# FOTA_MicroController.net
KiCad netlist of a schematic drawn in Altium Designer
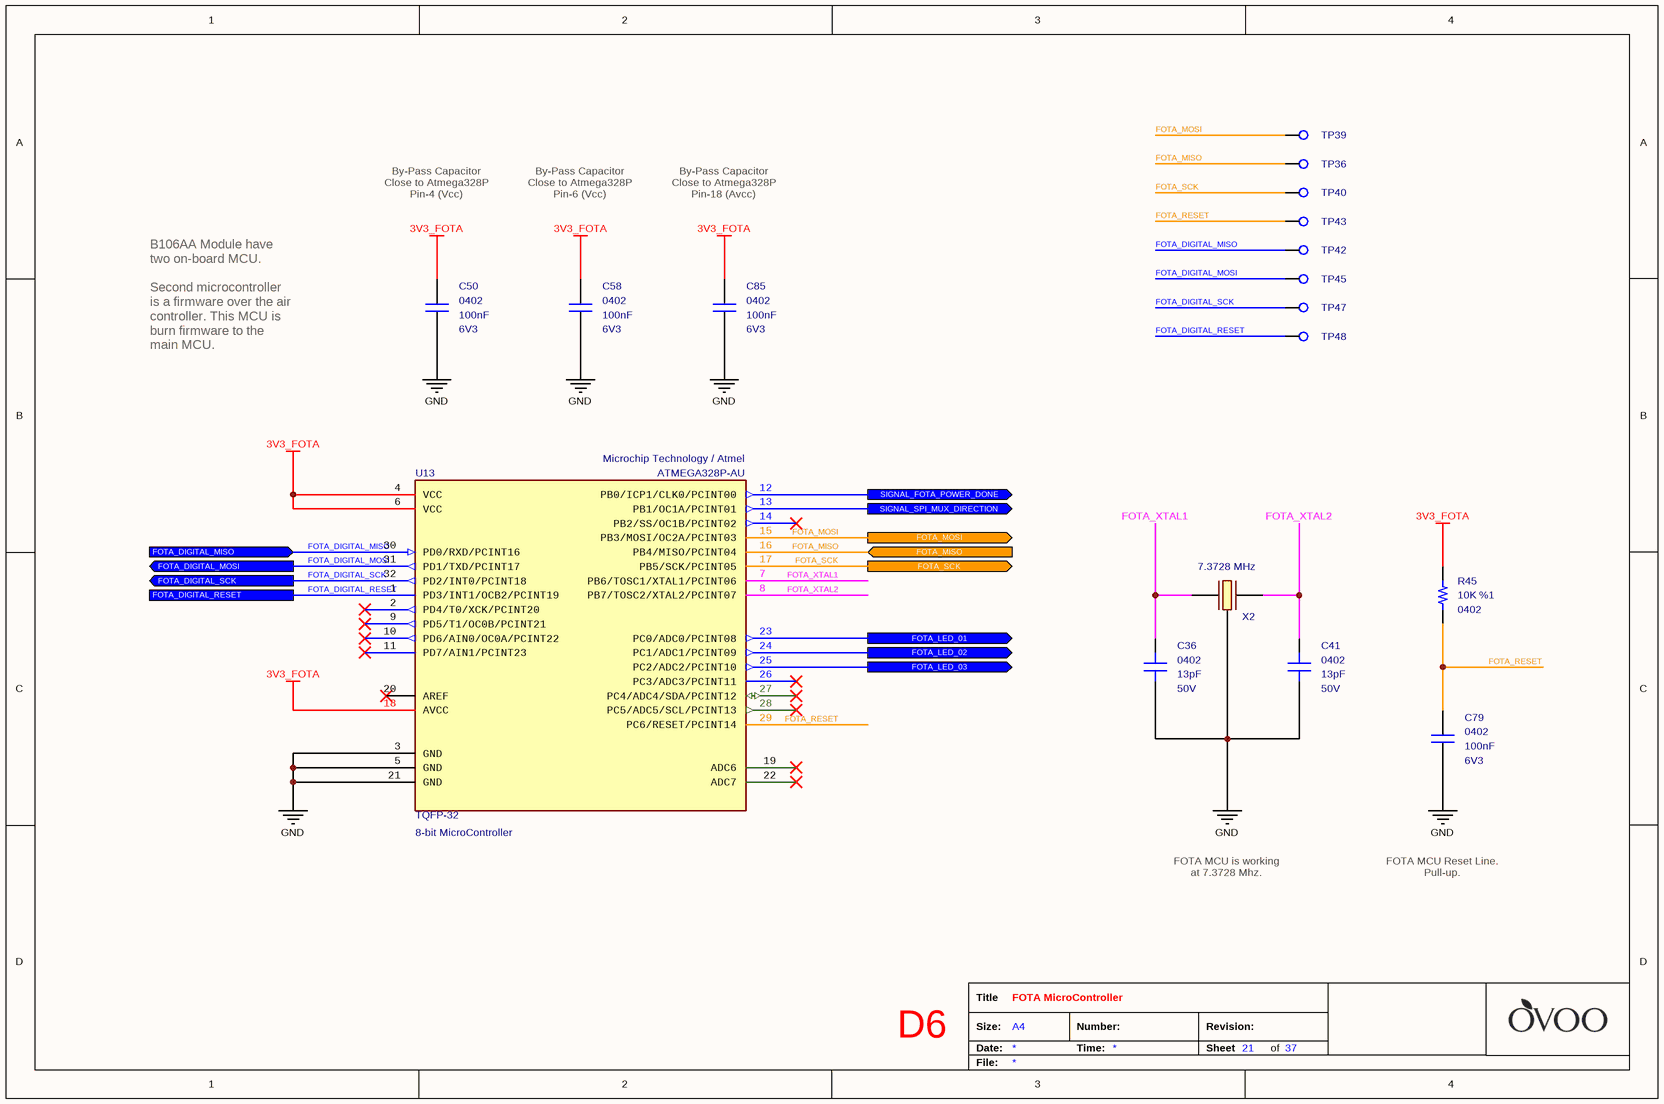
[diagram p0: FOTA MicroController.SchDoc]

(export (version "E")
  (design (tool "Eeschema 10.0.6"))
  (components
    (comp (ref "C36")
      (value "13pF")
      (footprint "CAPACITOR_0402")
      (description "Capacitor - 13pF [0402] (Ceramic)")
      (fields
        (field (name "MANUFACTURER_PART_NUMBER") "CBR04C130F5GAC")
        (field (name "MOUSER_PART_NUMBER") "80-CBR04C130F5GAC")
        (field (name "VOLTAGE") "50V")
        (field (name "CASE") "0402")
      )
      (libsource (lib "Ovoo_Schematic") (part "Capacitor - 13pF [0402-50V)"))
    )
    (comp (ref "C41")
      (value "13pF")
      (footprint "CAPACITOR_0402")
      (description "Capacitor - 13pF [0402] (Ceramic)")
      (fields
        (field (name "MANUFACTURER_PART_NUMBER") "CBR04C130F5GAC")
        (field (name "MOUSER_PART_NUMBER") "80-CBR04C130F5GAC")
        (field (name "VOLTAGE") "50V")
        (field (name "CASE") "0402")
      )
      (libsource (lib "Ovoo_Schematic") (part "Capacitor - 13pF [0402-50V)"))
    )
    (comp (ref "C50")
      (value "100nF")
      (footprint "CAPACITOR_0402")
      (description "Capacitor - 100nF [0402-6V3] (Ceramic)")
      (fields
        (field (name "MANUFACTURER_PART_NUMBER") "04026D104KAT4A")
        (field (name "MOUSER_PART_NUMBER") "581-04026D104KAT4A")
        (field (name "CASE") "0402")
        (field (name "VOLTAGE") "6V3")
      )
      (libsource (lib "Ovoo_Schematic") (part "Capacitor - 100nF [0402-6V3]"))
    )
    (comp (ref "C58")
      (value "100nF")
      (footprint "CAPACITOR_0402")
      (description "Capacitor - 100nF [0402-6V3] (Ceramic)")
      (fields
        (field (name "MANUFACTURER_PART_NUMBER") "04026D104KAT4A")
        (field (name "MOUSER_PART_NUMBER") "581-04026D104KAT4A")
        (field (name "CASE") "0402")
        (field (name "VOLTAGE") "6V3")
      )
      (libsource (lib "Ovoo_Schematic") (part "Capacitor - 100nF [0402-6V3]"))
    )
    (comp (ref "C79")
      (value "100nF")
      (footprint "CAPACITOR_0402")
      (description "Capacitor - 100nF [0402-6V3] (Ceramic)")
      (fields
        (field (name "MANUFACTURER_PART_NUMBER") "04026D104KAT4A")
        (field (name "MOUSER_PART_NUMBER") "581-04026D104KAT4A")
        (field (name "CASE") "0402")
        (field (name "VOLTAGE") "6V3")
      )
      (libsource (lib "Ovoo_Schematic") (part "Capacitor - 100nF [0402-6V3]"))
    )
    (comp (ref "C85")
      (value "100nF")
      (footprint "CAPACITOR_0402")
      (description "Capacitor - 100nF [0402-6V3] (Ceramic)")
      (fields
        (field (name "MANUFACTURER_PART_NUMBER") "04026D104KAT4A")
        (field (name "MOUSER_PART_NUMBER") "581-04026D104KAT4A")
        (field (name "CASE") "0402")
        (field (name "VOLTAGE") "6V3")
      )
      (libsource (lib "Ovoo_Schematic") (part "Capacitor - 100nF [0402-6V3]"))
    )
    (comp (ref "R45")
      (value "10K")
      (footprint "RESISTOR_0402")
      (description "Thick Film Resistors - SMD 1/16 W 10 Kohms 1%")
      (fields
        (field (name "MANUFACTURER_PART_NUMBER") "CRCW040210K0FKED")
        (field (name "MOUSER_PART_NUMBER") "71-CRCW0402-10K-E3")
        (field (name "TOLERANCE") "%1")
        (field (name "CASE") "0402")
      )
      (libsource (lib "Ovoo_Schematic") (part "Resistor - 10K"))
    )
    (comp (ref "TP36")
      (value "PCB - Test Point")
      (footprint "Test_Pad - Hole")
      (description "Test Point")
      (libsource (lib "Ovoo_Schematic") (part "PCB - Test Point"))
    )
    (comp (ref "TP39")
      (value "PCB - Test Point")
      (footprint "Test_Pad - Hole")
      (description "Test Point")
      (libsource (lib "Ovoo_Schematic") (part "PCB - Test Point"))
    )
    (comp (ref "TP40")
      (value "PCB - Test Point")
      (footprint "Test_Pad - Hole")
      (description "Test Point")
      (libsource (lib "Ovoo_Schematic") (part "PCB - Test Point"))
    )
    (comp (ref "TP42")
      (value "PCB - Test Point")
      (footprint "Test_Pad - Hole")
      (description "Test Point")
      (libsource (lib "Ovoo_Schematic") (part "PCB - Test Point"))
    )
    (comp (ref "TP43")
      (value "PCB - Test Point")
      (footprint "Test_Pad - Hole")
      (description "Test Point")
      (libsource (lib "Ovoo_Schematic") (part "PCB - Test Point"))
    )
    (comp (ref "TP45")
      (value "PCB - Test Point")
      (footprint "Test_Pad - Hole")
      (description "Test Point")
      (libsource (lib "Ovoo_Schematic") (part "PCB - Test Point"))
    )
    (comp (ref "TP47")
      (value "PCB - Test Point")
      (footprint "Test_Pad - Hole")
      (description "Test Point")
      (libsource (lib "Ovoo_Schematic") (part "PCB - Test Point"))
    )
    (comp (ref "TP48")
      (value "PCB - Test Point")
      (footprint "Test_Pad - Hole")
      (description "Test Point")
      (libsource (lib "Ovoo_Schematic") (part "PCB - Test Point"))
    )
    (comp (ref "U13")
      (value "8-bit MicroController")
      (footprint "TQFP32")
      (description "8-bit Microcontrollers - MCU 32KB In-system Flash 20MHz 1.8V-5.5V")
      (fields
        (field (name "MOUSER_PART_NUMBER") "556-ATMEGA328P-AU")
        (field (name "MANUFACTURER_PART_NUMBER") "ATMEGA328P-AU")
        (field (name "MANUFACTURER_NAME") "Microchip Technology / Atmel")
        (field (name "CASE") "TQFP-32")
      )
      (libsource (lib "Ovoo_Schematic") (part "IC - ATMEGA328P"))
    )
    (comp (ref "X2")
      (value "7.3728 MHz")
      (footprint "ABRACON_CRYSTAL")
      (description "Crystals 7.3728MHz 18pF -40C +85C")
      (fields
        (field (name "MANUFACTURER_PART_NUMBER") "ABMM2-7.3728MHZ-E2-T")
        (field (name "MOUSER_PART_NUMBER") "815-ABMM2-7.3-E2-T")
      )
      (libsource (lib "Ovoo_Schematic") (part "Crystal - 7.3728 MHz (Abracon)"))
    )
  )
  (nets
    (net (code "1") (name "/FOTA_DIGITAL_MISO") (class "Default")
      (node (ref "TP42") (pin "1") (pinfunction "1_1") (pintype "passive"))
      (node (ref "U13") (pin "30") (pinfunction "PD0/RXD/PCINT16_30") (pintype "input"))
    )
    (net (code "2") (name "/FOTA_DIGITAL_MOSI") (class "Default")
      (node (ref "TP45") (pin "1") (pinfunction "1_1") (pintype "passive"))
      (node (ref "U13") (pin "31") (pinfunction "PD1/TXD/PCINT17_31") (pintype "output"))
    )
    (net (code "3") (name "/FOTA_DIGITAL_RESET") (class "Default")
      (node (ref "TP48") (pin "1") (pinfunction "1_1") (pintype "passive"))
      (node (ref "U13") (pin "1") (pinfunction "PD3/INT1/OCB2/PCINT19_1") (pintype "passive"))
    )
    (net (code "4") (name "/FOTA_DIGITAL_SCK") (class "Default")
      (node (ref "TP47") (pin "1") (pinfunction "1_1") (pintype "passive"))
      (node (ref "U13") (pin "32") (pinfunction "PD2/INT0/PCINT18_32") (pintype "output"))
    )
    (net (code "5") (name "/FOTA_LED_01") (class "Default")
      (node (ref "U13") (pin "23") (pinfunction "PC0/ADC0/PCINT08_23") (pintype "output"))
    )
    (net (code "6") (name "/FOTA_LED_02") (class "Default")
      (node (ref "U13") (pin "24") (pinfunction "PC1/ADC1/PCINT09_24") (pintype "output"))
    )
    (net (code "7") (name "/FOTA_LED_03") (class "Default")
      (node (ref "U13") (pin "25") (pinfunction "PC2/ADC2/PCINT10_25") (pintype "output"))
    )
    (net (code "8") (name "/FOTA_MISO") (class "Default")
      (node (ref "TP36") (pin "1") (pinfunction "1_1") (pintype "passive"))
      (node (ref "U13") (pin "16") (pinfunction "PB4/MISO/PCINT04_16") (pintype "passive"))
    )
    (net (code "9") (name "/FOTA_MOSI") (class "Default")
      (node (ref "TP39") (pin "1") (pinfunction "1_1") (pintype "passive"))
      (node (ref "U13") (pin "15") (pinfunction "PB3/MOSI/OC2A/PCINT03_15") (pintype "passive"))
    )
    (net (code "10") (name "/FOTA_RESET") (class "Default")
      (node (ref "C79") (pin "2") (pinfunction "2_2") (pintype "passive"))
      (node (ref "R45") (pin "1") (pinfunction "1_1") (pintype "passive"))
      (node (ref "TP43") (pin "1") (pinfunction "1_1") (pintype "passive"))
      (node (ref "U13") (pin "29") (pinfunction "PC6/RESET/PCINT14_29") (pintype "passive"))
    )
    (net (code "11") (name "/FOTA_SCK") (class "Default")
      (node (ref "TP40") (pin "1") (pinfunction "1_1") (pintype "passive"))
      (node (ref "U13") (pin "17") (pinfunction "PB5/SCK/PCINT05_17") (pintype "passive"))
    )
    (net (code "12") (name "/FOTA_XTAL1") (class "Default")
      (node (ref "C36") (pin "2") (pinfunction "2_2") (pintype "passive"))
      (node (ref "U13") (pin "7") (pinfunction "PB6/TOSC1/XTAL1/PCINT06_7") (pintype "passive"))
      (node (ref "X2") (pin "3") (pinfunction "OUT/IN_3") (pintype "passive"))
    )
    (net (code "13") (name "/FOTA_XTAL2") (class "Default")
      (node (ref "C41") (pin "2") (pinfunction "2_2") (pintype "passive"))
      (node (ref "U13") (pin "8") (pinfunction "PB7/TOSC2/XTAL2/PCINT07_8") (pintype "passive"))
      (node (ref "X2") (pin "1") (pinfunction "IN/OUT_1") (pintype "passive"))
    )
    (net (code "14") (name "/SIGNAL_FOTA_POWER_DONE") (class "Default")
      (node (ref "U13") (pin "12") (pinfunction "PB0/ICP1/CLK0/PCINT00_12") (pintype "output"))
    )
    (net (code "15") (name "/SIGNAL_SPI_MUX_DIRECTION") (class "Default")
      (node (ref "U13") (pin "13") (pinfunction "PB1/OC1A/PCINT01_13") (pintype "output"))
    )
    (net (code "16") (name "3V3_FOTA") (class "Default")
      (node (ref "C50") (pin "2") (pinfunction "2_2") (pintype "passive"))
      (node (ref "C58") (pin "2") (pinfunction "2_2") (pintype "passive"))
      (node (ref "C85") (pin "2") (pinfunction "2_2") (pintype "passive"))
      (node (ref "R45") (pin "2") (pinfunction "2_2") (pintype "passive"))
      (node (ref "U13") (pin "18") (pinfunction "AVCC_18") (pintype "passive"))
      (node (ref "U13") (pin "4") (pinfunction "VCC_4") (pintype "power_in"))
      (node (ref "U13") (pin "6") (pinfunction "VCC_6") (pintype "power_in"))
    )
    (net (code "17") (name "GND") (class "Default")
      (node (ref "C36") (pin "1") (pinfunction "1_1") (pintype "passive"))
      (node (ref "C41") (pin "1") (pinfunction "1_1") (pintype "passive"))
      (node (ref "C50") (pin "1") (pinfunction "1_1") (pintype "passive"))
      (node (ref "C58") (pin "1") (pinfunction "1_1") (pintype "passive"))
      (node (ref "C79") (pin "1") (pinfunction "1_1") (pintype "passive"))
      (node (ref "C85") (pin "1") (pinfunction "1_1") (pintype "passive"))
      (node (ref "U13") (pin "21") (pinfunction "GND_21") (pintype "power_in"))
      (node (ref "U13") (pin "3") (pinfunction "GND_3") (pintype "power_in"))
      (node (ref "U13") (pin "5") (pinfunction "GND_5") (pintype "power_in"))
      (node (ref "X2") (pin "2") (pinfunction "GND_2") (pintype "passive"))
    )
    (net (code "18") (name "unconnected-(U13-ADC6-Pad19)") (class "Default")
      (node (ref "U13") (pin "19") (pinfunction "ADC6_19") (pintype "passive+no_connect"))
    )
    (net (code "19") (name "unconnected-(U13-ADC7-Pad22)") (class "Default")
      (node (ref "U13") (pin "22") (pinfunction "ADC7_22") (pintype "passive+no_connect"))
    )
    (net (code "20") (name "unconnected-(U13-AREF-Pad20)") (class "Default")
      (node (ref "U13") (pin "20") (pinfunction "AREF_20") (pintype "passive+no_connect"))
    )
    (net (code "21") (name "unconnected-(U13-PB2{slash}SS{slash}OC1B{slash}PCINT02-Pad14)") (class "Default")
      (node (ref "U13") (pin "14") (pinfunction "PB2/SS/OC1B/PCINT02_14") (pintype "output+no_connect"))
    )
    (net (code "22") (name "unconnected-(U13-PC3{slash}ADC3{slash}PCINT11-Pad26)") (class "Default")
      (node (ref "U13") (pin "26") (pinfunction "PC3/ADC3/PCINT11_26") (pintype "passive+no_connect"))
    )
    (net (code "23") (name "unconnected-(U13-PC4{slash}ADC4{slash}SDA{slash}PCINT12-Pad27)") (class "Default")
      (node (ref "U13") (pin "27") (pinfunction "PC4/ADC4/SDA/PCINT12_27") (pintype "bidirectional+no_connect"))
    )
    (net (code "24") (name "unconnected-(U13-PC5{slash}ADC5{slash}SCL{slash}PCINT13-Pad28)") (class "Default")
      (node (ref "U13") (pin "28") (pinfunction "PC5/ADC5/SCL/PCINT13_28") (pintype "output+no_connect"))
    )
    (net (code "25") (name "unconnected-(U13-PD4{slash}T0{slash}XCK{slash}PCINT20-Pad2)") (class "Default")
      (node (ref "U13") (pin "2") (pinfunction "PD4/T0/XCK/PCINT20_2") (pintype "output+no_connect"))
    )
    (net (code "26") (name "unconnected-(U13-PD5{slash}T1{slash}OC0B{slash}PCINT21-Pad9)") (class "Default")
      (node (ref "U13") (pin "9") (pinfunction "PD5/T1/OC0B/PCINT21_9") (pintype "output+no_connect"))
    )
    (net (code "27") (name "unconnected-(U13-PD6{slash}AIN0{slash}OC0A{slash}PCINT22-Pad10)") (class "Default")
      (node (ref "U13") (pin "10") (pinfunction "PD6/AIN0/OC0A/PCINT22_10") (pintype "output+no_connect"))
    )
    (net (code "28") (name "unconnected-(U13-PD7{slash}AIN1{slash}PCINT23-Pad11)") (class "Default")
      (node (ref "U13") (pin "11") (pinfunction "PD7/AIN1/PCINT23_11") (pintype "passive+no_connect"))
    )
    (net (code "29") (name "unconnected-(X2-GND-Pad4)") (class "Default")
      (node (ref "X2") (pin "4") (pinfunction "GND_4") (pintype "passive"))
    )
  )
)
